# lpc134x.net
KiCad netlist of a schematic drawn in EAGLE
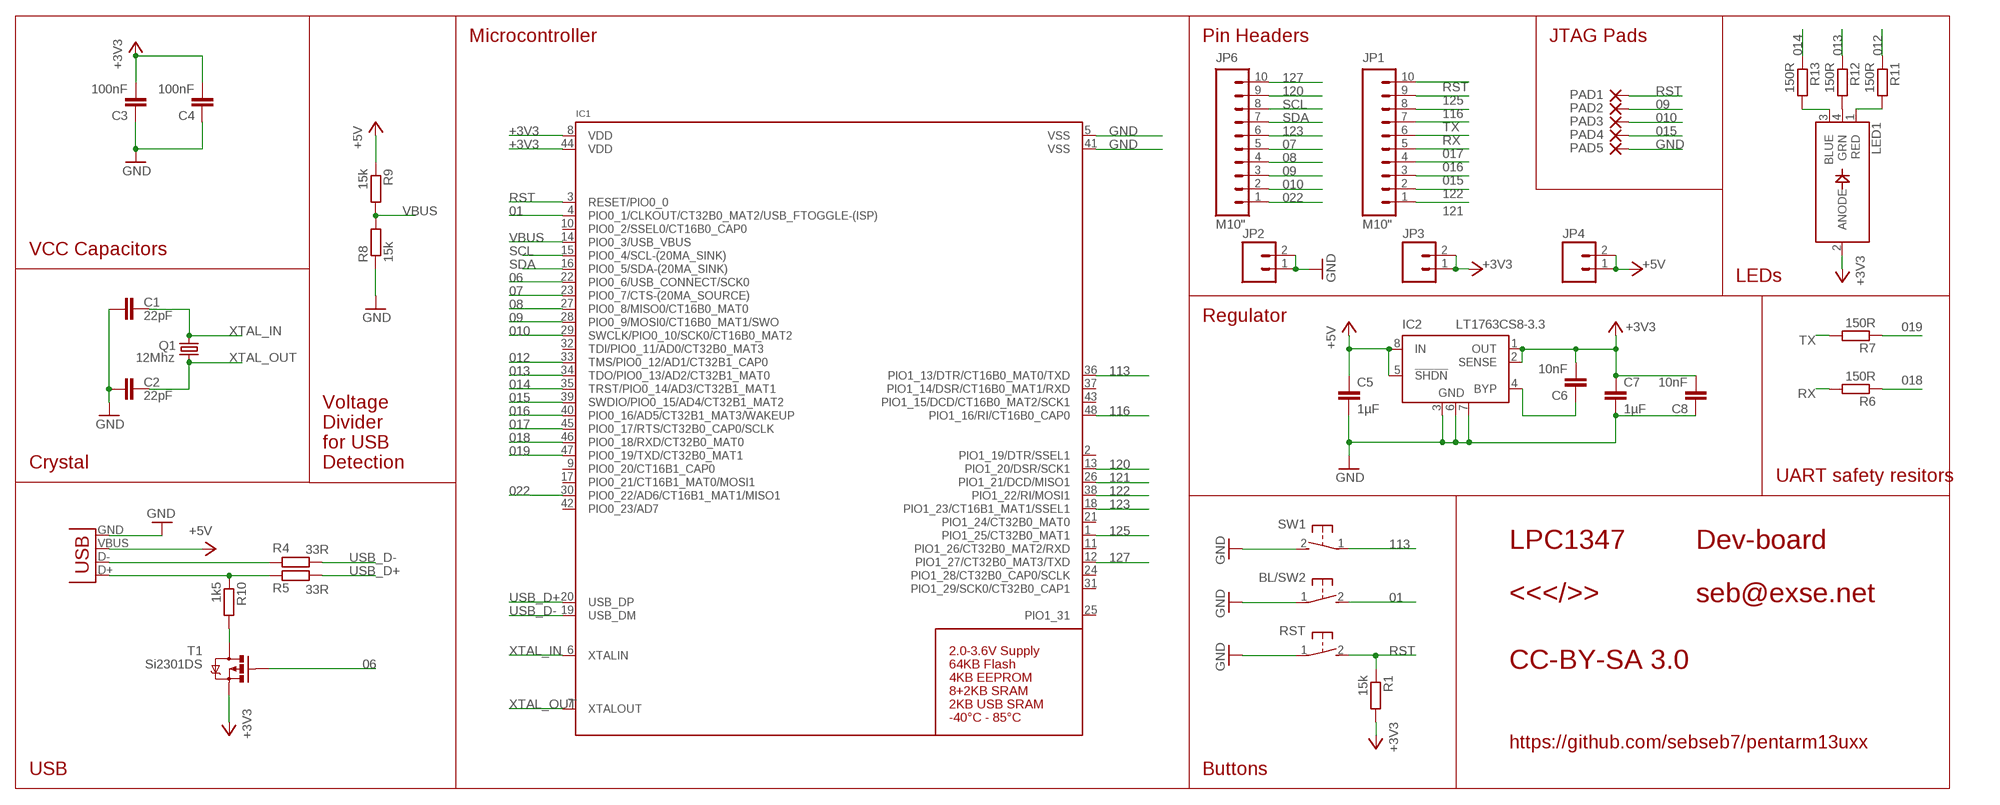
[diagram p0: schematic, sheet 1]

(export (version "E")
  (design (tool "Eeschema 10.0.6"))
  (components
    (comp (ref "BL/SW2")
      (value "SWITCH_MCTAEF")
      (footprint "eagle-import:SWITCH_MCTAEF")
      (libsource (lib "eagle-import") (part "SWITCH_MCTAEF"))
    )
    (comp (ref "C1")
      (value "22pF")
      (footprint "eagle-import:C0402")
      (libsource (lib "eagle-import") (part "C-EUC0402"))
    )
    (comp (ref "C2")
      (value "22pF")
      (footprint "eagle-import:C0402")
      (libsource (lib "eagle-import") (part "C-EUC0402"))
    )
    (comp (ref "C3")
      (value "100nF")
      (footprint "eagle-import:C0402")
      (libsource (lib "eagle-import") (part "C-EUC0402"))
    )
    (comp (ref "C4")
      (value "100nF")
      (footprint "eagle-import:C0402")
      (libsource (lib "eagle-import") (part "C-EUC0402"))
    )
    (comp (ref "C5")
      (value "1µF")
      (footprint "eagle-import:0805")
      (libsource (lib "eagle-import") (part "CAP0805"))
    )
    (comp (ref "C6")
      (value "10nF")
      (footprint "eagle-import:C0402")
      (libsource (lib "eagle-import") (part "C-EUC0402"))
    )
    (comp (ref "C7")
      (value "1µF")
      (footprint "eagle-import:0805")
      (libsource (lib "eagle-import") (part "CAP0805"))
    )
    (comp (ref "C8")
      (value "10nF")
      (footprint "eagle-import:C0402")
      (libsource (lib "eagle-import") (part "C-EUC0402"))
    )
    (comp (ref "IC1")
      (value "LPC1347_QFP48")
      (footprint "eagle-import:LQFP48")
      (libsource (lib "eagle-import") (part "LPC1347_QFP48"))
    )
    (comp (ref "IC2")
      (value "LT1763CS8-3.3")
      (footprint "eagle-import:SOIC8")
      (libsource (lib "eagle-import") (part "LT1763CS8-3.3"))
    )
    (comp (ref "JP1")
      (value "M10\"")
      (footprint "eagle-import:1X10")
      (libsource (lib "eagle-import") (part "M10{dblquote}"))
    )
    (comp (ref "JP2")
      (value "M02PTH")
      (footprint "eagle-import:1X02")
      (libsource (lib "eagle-import") (part "M02PTH"))
    )
    (comp (ref "JP3")
      (value "M02PTH")
      (footprint "eagle-import:1X02")
      (libsource (lib "eagle-import") (part "M02PTH"))
    )
    (comp (ref "JP4")
      (value "M02PTH")
      (footprint "eagle-import:1X02")
      (libsource (lib "eagle-import") (part "M02PTH"))
    )
    (comp (ref "JP6")
      (value "M10\"")
      (footprint "eagle-import:1X10")
      (libsource (lib "eagle-import") (part "M10{dblquote}"))
    )
    (comp (ref "LED1")
      (value "LED_RGB_PLCC4")
      (footprint "eagle-import:RGBLED_PLCC4")
      (libsource (lib "eagle-import") (part "LED_RGB_PLCC4"))
    )
    (comp (ref "PAD1")
      (value "WIREPADSMD1,27-254")
      (footprint "eagle-import:SMD1,27-2,54")
      (libsource (lib "eagle-import") (part "WIREPADSMD1,27-254"))
    )
    (comp (ref "PAD2")
      (value "WIREPADSMD1,27-254")
      (footprint "eagle-import:SMD1,27-2,54")
      (libsource (lib "eagle-import") (part "WIREPADSMD1,27-254"))
    )
    (comp (ref "PAD3")
      (value "WIREPADSMD1,27-254")
      (footprint "eagle-import:SMD1,27-2,54")
      (libsource (lib "eagle-import") (part "WIREPADSMD1,27-254"))
    )
    (comp (ref "PAD4")
      (value "WIREPADSMD1,27-254")
      (footprint "eagle-import:SMD1,27-2,54")
      (libsource (lib "eagle-import") (part "WIREPADSMD1,27-254"))
    )
    (comp (ref "PAD5")
      (value "WIREPADSMD1,27-254")
      (footprint "eagle-import:SMD1,27-2,54")
      (libsource (lib "eagle-import") (part "WIREPADSMD1,27-254"))
    )
    (comp (ref "Q1")
      (value "12Mhz")
      (footprint "eagle-import:MT")
      (libsource (lib "eagle-import") (part "MT-OSCILLATOR"))
    )
    (comp (ref "R1")
      (value "15k")
      (footprint "eagle-import:R0402")
      (libsource (lib "eagle-import") (part "R-EU_R0402"))
    )
    (comp (ref "R4")
      (value "33R")
      (footprint "eagle-import:R0402")
      (libsource (lib "eagle-import") (part "R-EU_R0402"))
    )
    (comp (ref "R5")
      (value "33R")
      (footprint "eagle-import:R0402")
      (libsource (lib "eagle-import") (part "R-EU_R0402"))
    )
    (comp (ref "R6")
      (value "150R")
      (footprint "eagle-import:R0402")
      (libsource (lib "eagle-import") (part "R-EU_R0402"))
    )
    (comp (ref "R7")
      (value "150R")
      (footprint "eagle-import:R0402")
      (libsource (lib "eagle-import") (part "R-EU_R0402"))
    )
    (comp (ref "R8")
      (value "15k")
      (footprint "eagle-import:R0402")
      (libsource (lib "eagle-import") (part "R-EU_R0402"))
    )
    (comp (ref "R9")
      (value "15k")
      (footprint "eagle-import:R0402")
      (libsource (lib "eagle-import") (part "R-EU_R0402"))
    )
    (comp (ref "R10")
      (value "1k5")
      (footprint "eagle-import:R0402")
      (libsource (lib "eagle-import") (part "R-EU_R0402"))
    )
    (comp (ref "R11")
      (value "150R")
      (footprint "eagle-import:R0402")
      (libsource (lib "eagle-import") (part "R-EU_R0402"))
    )
    (comp (ref "R12")
      (value "150R")
      (footprint "eagle-import:R0402")
      (libsource (lib "eagle-import") (part "R-EU_R0402"))
    )
    (comp (ref "R13")
      (value "150R")
      (footprint "eagle-import:R0402")
      (libsource (lib "eagle-import") (part "R-EU_R0402"))
    )
    (comp (ref "RST")
      (value "SWITCH_MCTAEF")
      (footprint "eagle-import:SWITCH_MCTAEF")
      (libsource (lib "eagle-import") (part "SWITCH_MCTAEF"))
    )
    (comp (ref "SW1")
      (value "SWITCH_MCTAEF")
      (footprint "eagle-import:SWITCH_MCTAEF")
      (libsource (lib "eagle-import") (part "SWITCH_MCTAEF"))
    )
    (comp (ref "T1")
      (value "Si2301DS")
      (footprint "eagle-import:SOT23")
      (libsource (lib "eagle-import") (part "MOSFET-PCHANNEL"))
    )
    (comp (ref "X2")
      (value "USB-SMD-NS")
      (footprint "eagle-import:USB-MINIB-NOSTOP")
      (libsource (lib "eagle-import") (part "USB-SMD-NS"))
    )
  )
  (nets
    (net (code "1") (name "+3V3") (class "Default")
      (node (ref "C3") (pin "2") (pinfunction "2_2") (pintype "passive"))
      (node (ref "C4") (pin "2") (pinfunction "2_2") (pintype "passive"))
      (node (ref "C6") (pin "2") (pinfunction "2_2") (pintype "passive"))
      (node (ref "C7") (pin "1") (pinfunction "1_1") (pintype "passive"))
      (node (ref "C8") (pin "2") (pinfunction "2_2") (pintype "passive"))
      (node (ref "IC1") (pin "44") (pinfunction "VDD_44") (pintype "power_in"))
      (node (ref "IC1") (pin "8") (pinfunction "VDD_8") (pintype "power_in"))
      (node (ref "IC2") (pin "1") (pinfunction "OUT_1") (pintype "passive"))
      (node (ref "IC2") (pin "2") (pinfunction "SENSE_2") (pintype "input"))
      (node (ref "JP3") (pin "1") (pinfunction "1_1") (pintype "passive"))
      (node (ref "JP3") (pin "2") (pinfunction "2_2") (pintype "passive"))
      (node (ref "LED1") (pin "2") (pinfunction "ANODE_2") (pintype "power_in"))
      (node (ref "R1") (pin "2") (pinfunction "2_2") (pintype "passive"))
      (node (ref "T1") (pin "2") (pinfunction "S_2") (pintype "passive"))
    )
    (net (code "2") (name "+5V") (class "Default")
      (node (ref "C5") (pin "1") (pinfunction "1_1") (pintype "passive"))
      (node (ref "IC2") (pin "5") (pinfunction "~{SHDN}_5") (pintype "input"))
      (node (ref "IC2") (pin "8") (pinfunction "IN_8") (pintype "input"))
      (node (ref "JP4") (pin "1") (pinfunction "1_1") (pintype "passive"))
      (node (ref "JP4") (pin "2") (pinfunction "2_2") (pintype "passive"))
      (node (ref "R9") (pin "1") (pinfunction "1_1") (pintype "passive"))
      (node (ref "X2") (pin "VBUS") (pinfunction "VBUS_VBUS") (pintype "bidirectional"))
    )
    (net (code "3") (name "/01") (class "Default")
      (node (ref "BL/SW2") (pin "2") (pinfunction "2_2") (pintype "passive"))
      (node (ref "IC1") (pin "4") (pinfunction "PIO0_1/CLKOUT/CT32B0_MAT2/USB_FTOGGLE-(ISP)_4") (pintype "bidirectional"))
    )
    (net (code "4") (name "/06") (class "Default")
      (node (ref "IC1") (pin "22") (pinfunction "PIO0_6/USB_CONNECT/SCK0_22") (pintype "bidirectional"))
      (node (ref "T1") (pin "1") (pinfunction "G_1") (pintype "passive"))
    )
    (net (code "5") (name "/07") (class "Default")
      (node (ref "IC1") (pin "23") (pinfunction "PIO0_7/CTS-(20MA_SOURCE)_23") (pintype "bidirectional"))
      (node (ref "JP6") (pin "5") (pinfunction "5_5") (pintype "passive"))
    )
    (net (code "6") (name "/08") (class "Default")
      (node (ref "IC1") (pin "27") (pinfunction "PIO0_8/MISO0/CT16B0_MAT0_27") (pintype "bidirectional"))
      (node (ref "JP6") (pin "4") (pinfunction "4_4") (pintype "passive"))
    )
    (net (code "7") (name "/09") (class "Default")
      (node (ref "IC1") (pin "28") (pinfunction "PIO0_9/MOSI0/CT16B0_MAT1/SWO_28") (pintype "bidirectional"))
      (node (ref "JP6") (pin "3") (pinfunction "3_3") (pintype "passive"))
      (node (ref "PAD2") (pin "1") (pinfunction "P_1") (pintype "passive"))
    )
    (net (code "8") (name "/010") (class "Default")
      (node (ref "IC1") (pin "29") (pinfunction "SWCLK/PIO0_10/SCK0/CT16B0_MAT2_29") (pintype "bidirectional"))
      (node (ref "JP6") (pin "2") (pinfunction "2_2") (pintype "passive"))
      (node (ref "PAD3") (pin "1") (pinfunction "P_1") (pintype "passive"))
    )
    (net (code "9") (name "/012") (class "Default")
      (node (ref "IC1") (pin "33") (pinfunction "TMS/PIO0_12/AD1/CT32B1_CAP0_33") (pintype "bidirectional"))
      (node (ref "R11") (pin "1") (pinfunction "1_1") (pintype "passive"))
    )
    (net (code "10") (name "/013") (class "Default")
      (node (ref "IC1") (pin "34") (pinfunction "TDO/PIO0_13/AD2/CT32B1_MAT0_34") (pintype "bidirectional"))
      (node (ref "R12") (pin "1") (pinfunction "1_1") (pintype "passive"))
    )
    (net (code "11") (name "/014") (class "Default")
      (node (ref "IC1") (pin "35") (pinfunction "TRST/PIO0_14/AD3/CT32B1_MAT1_35") (pintype "bidirectional"))
      (node (ref "R13") (pin "1") (pinfunction "1_1") (pintype "passive"))
    )
    (net (code "12") (name "/015") (class "Default")
      (node (ref "IC1") (pin "39") (pinfunction "SWDIO/PIO0_15/AD4/CT32B1_MAT2_39") (pintype "bidirectional"))
      (node (ref "JP1") (pin "3") (pinfunction "3_3") (pintype "passive"))
      (node (ref "PAD4") (pin "1") (pinfunction "P_1") (pintype "passive"))
    )
    (net (code "13") (name "/016") (class "Default")
      (node (ref "IC1") (pin "40") (pinfunction "PIO0_16/AD5/CT32B1_MAT3/WAKEUP_40") (pintype "bidirectional"))
      (node (ref "JP1") (pin "4") (pinfunction "4_4") (pintype "passive"))
    )
    (net (code "14") (name "/017") (class "Default")
      (node (ref "IC1") (pin "45") (pinfunction "PIO0_17/RTS/CT32B0_CAP0/SCLK_45") (pintype "bidirectional"))
      (node (ref "JP1") (pin "5") (pinfunction "5_5") (pintype "passive"))
    )
    (net (code "15") (name "/018") (class "Default")
      (node (ref "IC1") (pin "46") (pinfunction "PIO0_18/RXD/CT32B0_MAT0_46") (pintype "bidirectional"))
      (node (ref "R6") (pin "1") (pinfunction "1_1") (pintype "passive"))
    )
    (net (code "16") (name "/019") (class "Default")
      (node (ref "IC1") (pin "47") (pinfunction "PIO0_19/TXD/CT32B0_MAT1_47") (pintype "bidirectional"))
      (node (ref "R7") (pin "1") (pinfunction "1_1") (pintype "passive"))
    )
    (net (code "17") (name "/022") (class "Default")
      (node (ref "IC1") (pin "30") (pinfunction "PIO0_22/AD6/CT16B1_MAT1/MISO1_30") (pintype "bidirectional"))
      (node (ref "JP6") (pin "1") (pinfunction "1_1") (pintype "passive"))
    )
    (net (code "18") (name "/113") (class "Default")
      (node (ref "IC1") (pin "36") (pinfunction "PIO1_13/DTR/CT16B0_MAT0/TXD_36") (pintype "bidirectional"))
      (node (ref "SW1") (pin "1") (pinfunction "1_1") (pintype "passive"))
    )
    (net (code "19") (name "/116") (class "Default")
      (node (ref "IC1") (pin "48") (pinfunction "PIO1_16/RI/CT16B0_CAP0_48") (pintype "bidirectional"))
      (node (ref "JP1") (pin "8") (pinfunction "8_8") (pintype "passive"))
    )
    (net (code "20") (name "/120") (class "Default")
      (node (ref "IC1") (pin "13") (pinfunction "PIO1_20/DSR/SCK1_13") (pintype "bidirectional"))
      (node (ref "JP6") (pin "9") (pinfunction "9_9") (pintype "passive"))
    )
    (net (code "21") (name "/121") (class "Default")
      (node (ref "IC1") (pin "26") (pinfunction "PIO1_21/DCD/MISO1_26") (pintype "bidirectional"))
      (node (ref "JP1") (pin "1") (pinfunction "1_1") (pintype "passive"))
    )
    (net (code "22") (name "/122") (class "Default")
      (node (ref "IC1") (pin "38") (pinfunction "PIO1_22/RI/MOSI1_38") (pintype "bidirectional"))
      (node (ref "JP1") (pin "2") (pinfunction "2_2") (pintype "passive"))
    )
    (net (code "23") (name "/123") (class "Default")
      (node (ref "IC1") (pin "18") (pinfunction "PIO1_23/CT16B1_MAT1/SSEL1_18") (pintype "bidirectional"))
      (node (ref "JP6") (pin "6") (pinfunction "6_6") (pintype "passive"))
    )
    (net (code "24") (name "/125") (class "Default")
      (node (ref "IC1") (pin "1") (pinfunction "PIO1_25/CT32B0_MAT1_1") (pintype "bidirectional"))
      (node (ref "JP1") (pin "9") (pinfunction "9_9") (pintype "passive"))
    )
    (net (code "25") (name "/127") (class "Default")
      (node (ref "IC1") (pin "12") (pinfunction "PIO1_27/CT32B0_MAT3/TXD_12") (pintype "bidirectional"))
      (node (ref "JP6") (pin "10") (pinfunction "10_10") (pintype "passive"))
    )
    (net (code "26") (name "/RST") (class "Default")
      (node (ref "IC1") (pin "3") (pinfunction "RESET/PIO0_0_3") (pintype "bidirectional"))
      (node (ref "JP1") (pin "10") (pinfunction "10_10") (pintype "passive"))
      (node (ref "PAD1") (pin "1") (pinfunction "P_1") (pintype "passive"))
      (node (ref "R1") (pin "1") (pinfunction "1_1") (pintype "passive"))
      (node (ref "RST") (pin "2") (pinfunction "2_2") (pintype "passive"))
    )
    (net (code "27") (name "/RX") (class "Default")
      (node (ref "JP1") (pin "6") (pinfunction "6_6") (pintype "passive"))
      (node (ref "R6") (pin "2") (pinfunction "2_2") (pintype "passive"))
    )
    (net (code "28") (name "/SCL") (class "Default")
      (node (ref "IC1") (pin "15") (pinfunction "PIO0_4/SCL-(20MA_SINK)_15") (pintype "bidirectional"))
      (node (ref "JP6") (pin "8") (pinfunction "8_8") (pintype "passive"))
    )
    (net (code "29") (name "/SDA") (class "Default")
      (node (ref "IC1") (pin "16") (pinfunction "PIO0_5/SDA-(20MA_SINK)_16") (pintype "bidirectional"))
      (node (ref "JP6") (pin "7") (pinfunction "7_7") (pintype "passive"))
    )
    (net (code "30") (name "/TX") (class "Default")
      (node (ref "JP1") (pin "7") (pinfunction "7_7") (pintype "passive"))
      (node (ref "R7") (pin "2") (pinfunction "2_2") (pintype "passive"))
    )
    (net (code "31") (name "/USB_D+") (class "Default")
      (node (ref "IC1") (pin "20") (pinfunction "USB_DP_20") (pintype "bidirectional"))
      (node (ref "R5") (pin "1") (pinfunction "1_1") (pintype "passive"))
    )
    (net (code "32") (name "/USB_D-") (class "Default")
      (node (ref "IC1") (pin "19") (pinfunction "USB_DM_19") (pintype "bidirectional"))
      (node (ref "R4") (pin "1") (pinfunction "1_1") (pintype "passive"))
    )
    (net (code "33") (name "/VBUS") (class "Default")
      (node (ref "IC1") (pin "14") (pinfunction "PIO0_3/USB_VBUS_14") (pintype "bidirectional"))
      (node (ref "R8") (pin "2") (pinfunction "2_2") (pintype "passive"))
      (node (ref "R9") (pin "2") (pinfunction "2_2") (pintype "passive"))
    )
    (net (code "34") (name "/XTAL_IN") (class "Default")
      (node (ref "C1") (pin "2") (pinfunction "2_2") (pintype "passive"))
      (node (ref "IC1") (pin "6") (pinfunction "XTALIN_6") (pintype "bidirectional"))
      (node (ref "Q1") (pin "3") (pinfunction "2_3") (pintype "passive"))
    )
    (net (code "35") (name "/XTAL_OUT") (class "Default")
      (node (ref "C2") (pin "2") (pinfunction "2_2") (pintype "passive"))
      (node (ref "IC1") (pin "7") (pinfunction "XTALOUT_7") (pintype "bidirectional"))
      (node (ref "Q1") (pin "1") (pinfunction "1_1") (pintype "passive"))
    )
    (net (code "36") (name "GND") (class "Default")
      (node (ref "BL/SW2") (pin "1") (pinfunction "1_1") (pintype "passive"))
      (node (ref "C1") (pin "1") (pinfunction "1_1") (pintype "passive"))
      (node (ref "C2") (pin "1") (pinfunction "1_1") (pintype "passive"))
      (node (ref "C3") (pin "1") (pinfunction "1_1") (pintype "passive"))
      (node (ref "C4") (pin "1") (pinfunction "1_1") (pintype "passive"))
      (node (ref "C5") (pin "2") (pinfunction "2_2") (pintype "passive"))
      (node (ref "C7") (pin "2") (pinfunction "2_2") (pintype "passive"))
      (node (ref "C8") (pin "1") (pinfunction "1_1") (pintype "passive"))
      (node (ref "IC1") (pin "41") (pinfunction "VSS_41") (pintype "power_in"))
      (node (ref "IC1") (pin "5") (pinfunction "VSS_5") (pintype "power_in"))
      (node (ref "IC2") (pin "3") (pinfunction "GND_3") (pintype "power_in"))
      (node (ref "IC2") (pin "6") (pinfunction "GND_6") (pintype "power_in"))
      (node (ref "IC2") (pin "7") (pinfunction "GND_7") (pintype "power_in"))
      (node (ref "JP2") (pin "1") (pinfunction "1_1") (pintype "passive"))
      (node (ref "JP2") (pin "2") (pinfunction "2_2") (pintype "passive"))
      (node (ref "PAD5") (pin "1") (pinfunction "P_1") (pintype "passive"))
      (node (ref "R8") (pin "1") (pinfunction "1_1") (pintype "passive"))
      (node (ref "RST") (pin "1") (pinfunction "1_1") (pintype "passive"))
      (node (ref "SW1") (pin "2") (pinfunction "2_2") (pintype "passive"))
      (node (ref "X2") (pin "GND") (pinfunction "GND_GND") (pintype "bidirectional"))
    )
    (net (code "37") (name "Net-(IC2-BYP)") (class "Default")
      (node (ref "C6") (pin "1") (pinfunction "1_1") (pintype "passive"))
      (node (ref "IC2") (pin "4") (pinfunction "BYP_4") (pintype "input"))
    )
    (net (code "38") (name "Net-(LED1-BLUE)") (class "Default")
      (node (ref "LED1") (pin "3") (pinfunction "BLUE_3") (pintype "bidirectional"))
      (node (ref "R13") (pin "2") (pinfunction "2_2") (pintype "passive"))
    )
    (net (code "39") (name "Net-(LED1-GRN)") (class "Default")
      (node (ref "LED1") (pin "4") (pinfunction "GRN_4") (pintype "bidirectional"))
      (node (ref "R12") (pin "2") (pinfunction "2_2") (pintype "passive"))
    )
    (net (code "40") (name "Net-(LED1-RED)") (class "Default")
      (node (ref "LED1") (pin "1") (pinfunction "RED_1") (pintype "bidirectional"))
      (node (ref "R11") (pin "2") (pinfunction "2_2") (pintype "passive"))
    )
    (net (code "41") (name "Net-(R4-Pad2)") (class "Default")
      (node (ref "R4") (pin "2") (pinfunction "2_2") (pintype "passive"))
      (node (ref "X2") (pin "D-") (pinfunction "D-_D-") (pintype "bidirectional"))
    )
    (net (code "42") (name "Net-(R10-Pad1)") (class "Default")
      (node (ref "R10") (pin "1") (pinfunction "1_1") (pintype "passive"))
      (node (ref "R5") (pin "2") (pinfunction "2_2") (pintype "passive"))
      (node (ref "X2") (pin "D+") (pinfunction "D+_D+") (pintype "bidirectional"))
    )
    (net (code "43") (name "Net-(T1-D)") (class "Default")
      (node (ref "R10") (pin "2") (pinfunction "2_2") (pintype "passive"))
      (node (ref "T1") (pin "3") (pinfunction "D_3") (pintype "passive"))
    )
    (net (code "44") (name "unconnected-(IC1-PIO0_2{slash}SSEL0{slash}CT16B0_CAP0-Pad10)") (class "Default")
      (node (ref "IC1") (pin "10") (pinfunction "PIO0_2/SSEL0/CT16B0_CAP0_10") (pintype "bidirectional"))
    )
    (net (code "45") (name "unconnected-(IC1-PIO0_20{slash}CT16B1_CAP0-Pad9)") (class "Default")
      (node (ref "IC1") (pin "9") (pinfunction "PIO0_20/CT16B1_CAP0_9") (pintype "bidirectional"))
    )
    (net (code "46") (name "unconnected-(IC1-PIO0_21{slash}CT16B1_MAT0{slash}MOSI1-Pad17)") (class "Default")
      (node (ref "IC1") (pin "17") (pinfunction "PIO0_21/CT16B1_MAT0/MOSI1_17") (pintype "bidirectional"))
    )
    (net (code "47") (name "unconnected-(IC1-PIO0_23{slash}AD7-Pad42)") (class "Default")
      (node (ref "IC1") (pin "42") (pinfunction "PIO0_23/AD7_42") (pintype "bidirectional"))
    )
    (net (code "48") (name "unconnected-(IC1-PIO1_14{slash}DSR{slash}CT16B0_MAT1{slash}RXD-Pad37)") (class "Default")
      (node (ref "IC1") (pin "37") (pinfunction "PIO1_14/DSR/CT16B0_MAT1/RXD_37") (pintype "bidirectional"))
    )
    (net (code "49") (name "unconnected-(IC1-PIO1_15{slash}DCD{slash}CT16B0_MAT2{slash}SCK1-Pad43)") (class "Default")
      (node (ref "IC1") (pin "43") (pinfunction "PIO1_15/DCD/CT16B0_MAT2/SCK1_43") (pintype "bidirectional"))
    )
    (net (code "50") (name "unconnected-(IC1-PIO1_19{slash}DTR{slash}SSEL1-Pad2)") (class "Default")
      (node (ref "IC1") (pin "2") (pinfunction "PIO1_19/DTR/SSEL1_2") (pintype "bidirectional"))
    )
    (net (code "51") (name "unconnected-(IC1-PIO1_24{slash}CT32B0_MAT0-Pad21)") (class "Default")
      (node (ref "IC1") (pin "21") (pinfunction "PIO1_24/CT32B0_MAT0_21") (pintype "bidirectional"))
    )
    (net (code "52") (name "unconnected-(IC1-PIO1_26{slash}CT32B0_MAT2{slash}RXD-Pad11)") (class "Default")
      (node (ref "IC1") (pin "11") (pinfunction "PIO1_26/CT32B0_MAT2/RXD_11") (pintype "bidirectional"))
    )
    (net (code "53") (name "unconnected-(IC1-PIO1_28{slash}CT32B0_CAP0{slash}SCLK-Pad24)") (class "Default")
      (node (ref "IC1") (pin "24") (pinfunction "PIO1_28/CT32B0_CAP0/SCLK_24") (pintype "bidirectional"))
    )
    (net (code "54") (name "unconnected-(IC1-PIO1_29{slash}SCK0{slash}CT32B0_CAP1-Pad31)") (class "Default")
      (node (ref "IC1") (pin "31") (pinfunction "PIO1_29/SCK0/CT32B0_CAP1_31") (pintype "bidirectional"))
    )
    (net (code "55") (name "unconnected-(IC1-PIO1_31-Pad25)") (class "Default")
      (node (ref "IC1") (pin "25") (pinfunction "PIO1_31_25") (pintype "bidirectional"))
    )
    (net (code "56") (name "unconnected-(IC1-TDI{slash}PIO0_11{slash}AD0{slash}CT32B0_MAT3-Pad32)") (class "Default")
      (node (ref "IC1") (pin "32") (pinfunction "TDI/PIO0_11/AD0/CT32B0_MAT3_32") (pintype "bidirectional"))
    )
  )
)
